# LightLinkV2.net
KiCad netlist of a schematic drawn in Altium Designer
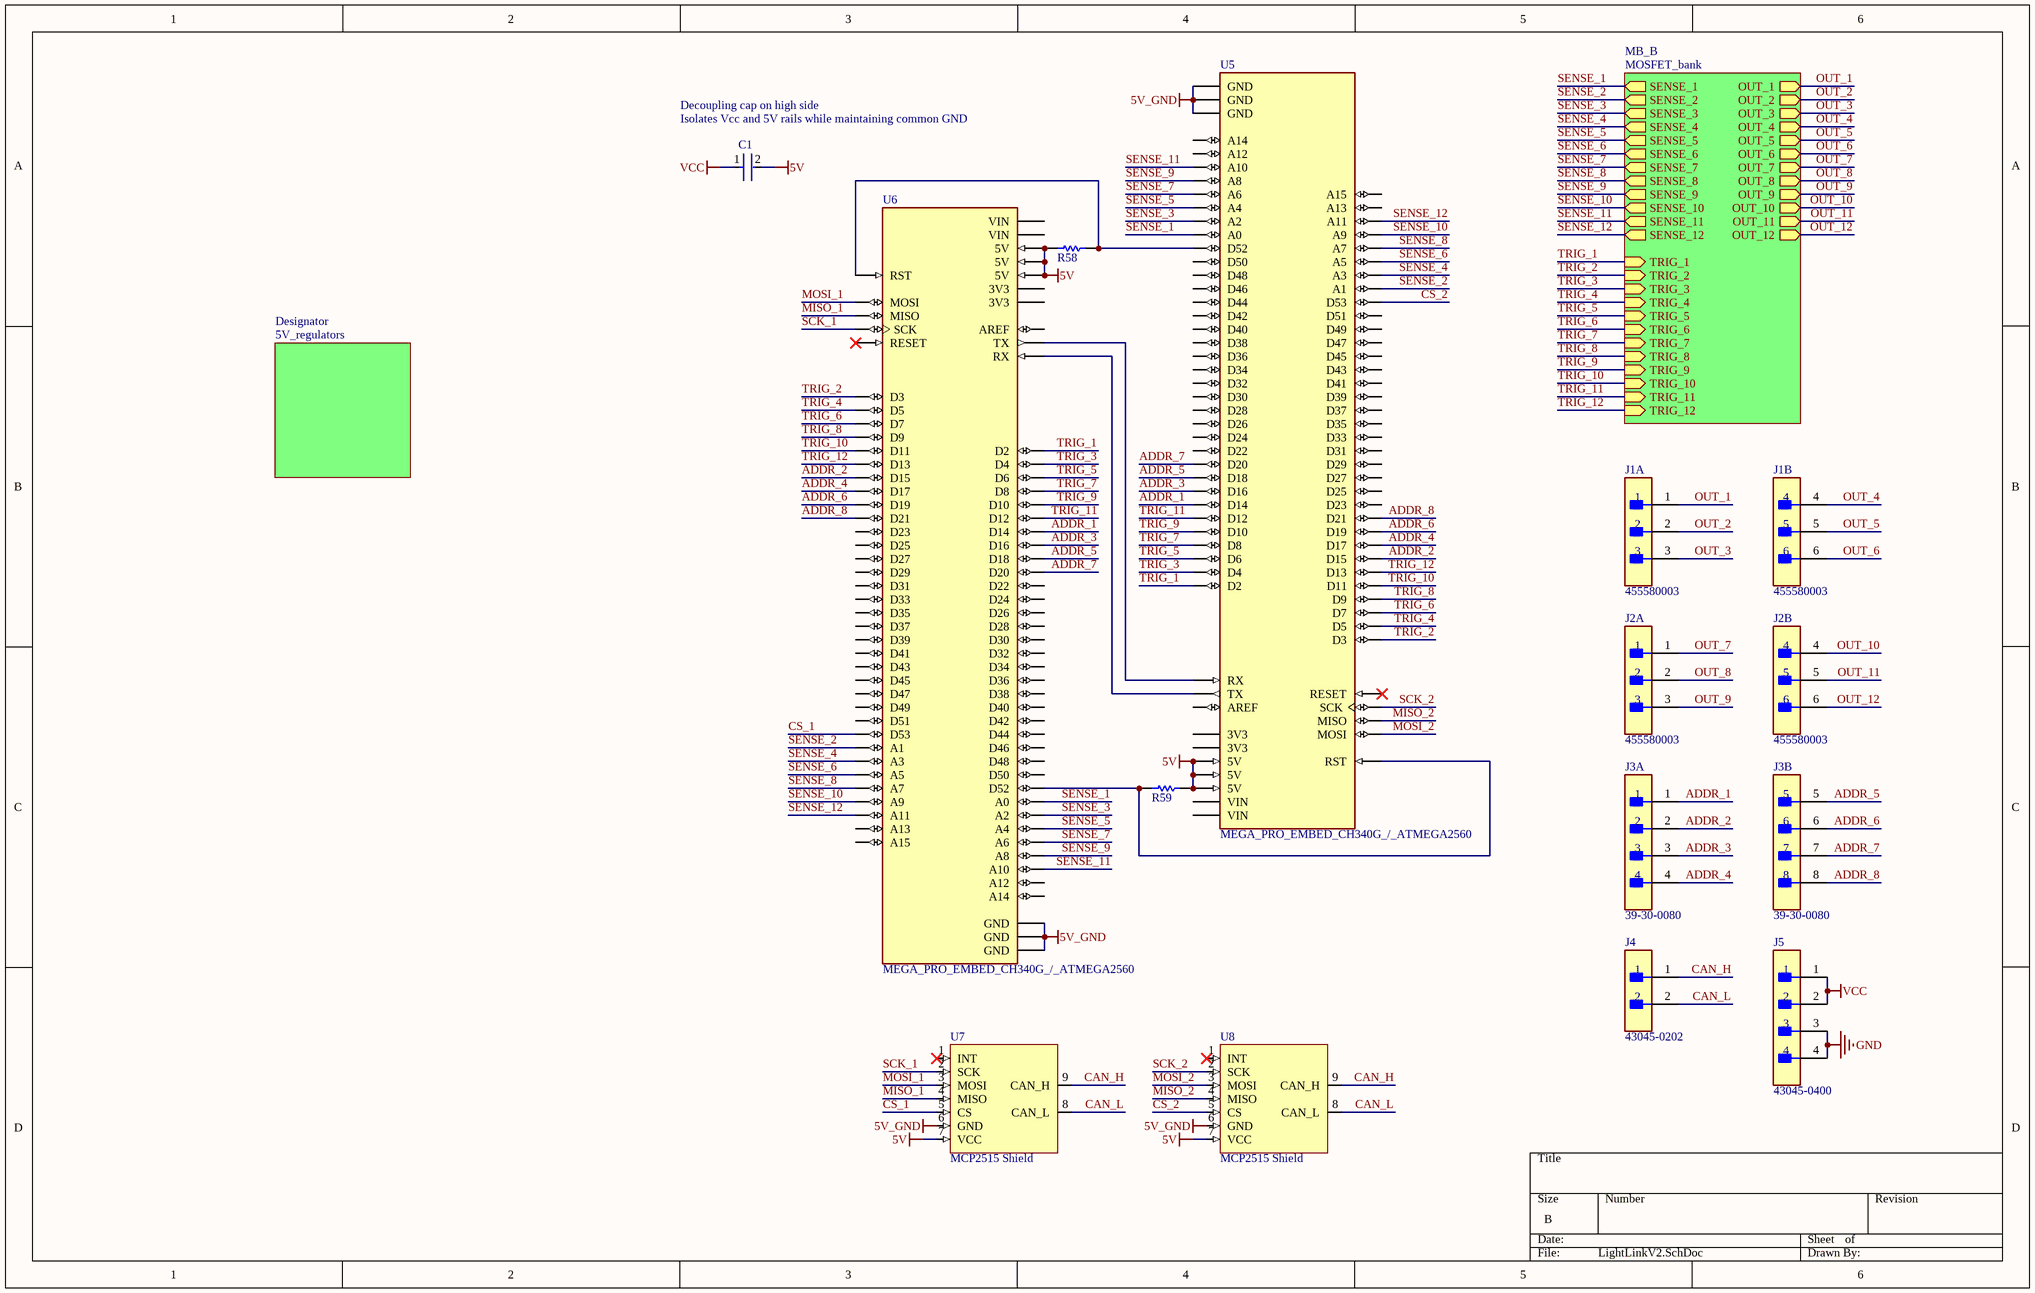
[diagram p0: LightLinkV2.SchDoc]

(export (version "E")
  (design (tool "Eeschema 10.0.6"))
  (components
    (comp (ref "C1")
      (value "C0603C103K5RACTU")
      (footprint "FP-C0603C-CF-MFG")
      (description "CAP CER 10000PF 50V X7R 0603")
      (fields
        (field (name "MANUFACTURER") "KEMET")
        (field (name "OCTOPART") "https://octopart.com/c0603c103k5ractu-kemet-133094")
      )
      (libsource (lib "Altium Content Vault") (part "b4654b650e69147ec39a6b967a45e02"))
    )
    (comp (ref "J1")
      (value "455580003")
      (footprint "FP-455580003-MFG")
      (description "CONN HEADER R/A 6POS 4.2MM")
      (fields
        (field (name "OCTOPART") "https://octopart.com/45558-0003-molex-7672845")
        (field (name "MANUFACTURER") "Molex")
      )
      (libsource (lib "Altium Content Vault") (part "bb9cbdb24149a20ba329b4e86909569"))
    )
    (comp (ref "J2")
      (value "455580003")
      (footprint "FP-455580003-MFG")
      (description "CONN HEADER R/A 6POS 4.2MM")
      (fields
        (field (name "OCTOPART") "https://octopart.com/45558-0003-molex-7672845")
        (field (name "MANUFACTURER") "Molex")
      )
      (libsource (lib "Altium Content Vault") (part "bb9cbdb24149a20ba329b4e86909569"))
    )
    (comp (ref "J3")
      (value "39-30-0080")
      (footprint "FP-39-30-0080-MFG")
      (description "CONN HEADER R/A 8POS 4.2MM")
      (libsource (lib "Altium Content Vault") (part "85438c39ca9ef07d43bb2e97c52bc44"))
    )
    (comp (ref "J4")
      (value "43045-0202")
      (footprint "FP-43045-0202-MFG")
      (description "CONN HEADER R/A 2POS")
      (libsource (lib "Altium Content Vault") (part "3bc925449376181038e59eaffc5286c"))
    )
    (comp (ref "J5")
      (value "43045-0400")
      (footprint "FP-43045-0400-MFG")
      (description "CONN HEADER R/A 4POS 3MM")
      (fields
        (field (name "MANUFACTURER") "Molex")
        (field (name "OCTOPART") "https://octopart.com/43045-0400-molex-287063")
      )
      (libsource (lib "Altium Content Vault") (part "c01754ab0efc13afb7424b896f394ef"))
    )
    (comp (ref "R58")
      (value "ERJ3EKF1002V")
      (footprint "RESC1609X55X30LL15T15")
      (description "Chip Resistor, 10 KOhm, +/- 1%, 0.1 W, -55 to 155 degC, 0603 (1608 Metric), RoHS, Tape and Reel")
      (fields (field (name "TOLERANCE") "1%") (field (name "MANUFACTURER") "Panasonic"))
      (libsource (lib "Altium Content Vault") (part "RES-2"))
    )
    (comp (ref "R59")
      (value "ERJ3EKF1002V")
      (footprint "RESC1609X55X30LL15T15")
      (description "Chip Resistor, 10 KOhm, +/- 1%, 0.1 W, -55 to 155 degC, 0603 (1608 Metric), RoHS, Tape and Reel")
      (fields (field (name "TOLERANCE") "1%") (field (name "MANUFACTURER") "Panasonic"))
      (libsource (lib "Altium Content Vault") (part "RES-2"))
    )
    (comp (ref "U5")
      (value "MEGA_PRO_EMBED_CH340G_/_ATMEGA2560")
      (footprint "MODULE_MEGA_PRO_EMBED_CH340G_/_ATMEGA2560")
      (description "Mega 2560 PRO (Embed) CH340G/ATmega2560-16AU")
      (libsource (lib "") (part "MEGA_PRO_EMBED_CH340G_/_ATMEGA2560_1"))
    )
    (comp (ref "U6")
      (value "MEGA_PRO_EMBED_CH340G_/_ATMEGA2560")
      (footprint "MODULE_MEGA_PRO_EMBED_CH340G_/_ATMEGA2560")
      (description "Mega 2560 PRO (Embed) CH340G/ATmega2560-16AU")
      (libsource (lib "uORocketry Hardware") (part "MEGA_PRO_EMBED_CH340G_/_ATMEGA2560"))
    )
    (comp (ref "U7")
      (value "MCP2515 Shield")
      (footprint "MCP2515 Shield-Footprint-1")
      (libsource (lib "uORocketry Hardware") (part "MCP2515 Shield Symbol"))
    )
    (comp (ref "U8")
      (value "MCP2515 Shield")
      (footprint "MCP2515 Shield-Footprint-1")
      (libsource (lib "uORocketry Hardware") (part "MCP2515 Shield Symbol"))
    )
  )
  (nets
    (net (code "1") (name "/ADDR_1") (class "Default")
      (node (ref "J3") (pin "1") (pinfunction "1_1") (pintype "passive"))
      (node (ref "U5") (pin "D14") (pinfunction "D14_D14") (pintype "bidirectional"))
      (node (ref "U6") (pin "D14") (pinfunction "D14_D14") (pintype "bidirectional"))
    )
    (net (code "2") (name "/ADDR_2") (class "Default")
      (node (ref "J3") (pin "2") (pinfunction "2_2") (pintype "passive"))
      (node (ref "U5") (pin "D15") (pinfunction "D15_D15") (pintype "bidirectional"))
      (node (ref "U6") (pin "D15") (pinfunction "D15_D15") (pintype "bidirectional"))
    )
    (net (code "3") (name "/ADDR_3") (class "Default")
      (node (ref "J3") (pin "3") (pinfunction "3_3") (pintype "passive"))
      (node (ref "U5") (pin "D16") (pinfunction "D16_D16") (pintype "bidirectional"))
      (node (ref "U6") (pin "D16") (pinfunction "D16_D16") (pintype "bidirectional"))
    )
    (net (code "4") (name "/ADDR_4") (class "Default")
      (node (ref "J3") (pin "4") (pinfunction "4_4") (pintype "passive"))
      (node (ref "U5") (pin "D17") (pinfunction "D17_D17") (pintype "bidirectional"))
      (node (ref "U6") (pin "D17") (pinfunction "D17_D17") (pintype "bidirectional"))
    )
    (net (code "5") (name "/ADDR_5") (class "Default")
      (node (ref "J3") (pin "5") (pinfunction "5_5") (pintype "passive"))
      (node (ref "U5") (pin "D18") (pinfunction "D18_D18") (pintype "bidirectional"))
      (node (ref "U6") (pin "D18") (pinfunction "D18_D18") (pintype "bidirectional"))
    )
    (net (code "6") (name "/ADDR_6") (class "Default")
      (node (ref "J3") (pin "6") (pinfunction "6_6") (pintype "passive"))
      (node (ref "U5") (pin "D19") (pinfunction "D19_D19") (pintype "bidirectional"))
      (node (ref "U6") (pin "D19") (pinfunction "D19_D19") (pintype "bidirectional"))
    )
    (net (code "7") (name "/ADDR_7") (class "Default")
      (node (ref "J3") (pin "7") (pinfunction "7_7") (pintype "passive"))
      (node (ref "U5") (pin "D20") (pinfunction "D20_D20") (pintype "bidirectional"))
      (node (ref "U6") (pin "D20") (pinfunction "D20_D20") (pintype "bidirectional"))
    )
    (net (code "8") (name "/ADDR_8") (class "Default")
      (node (ref "J3") (pin "8") (pinfunction "8_8") (pintype "passive"))
      (node (ref "U5") (pin "D21") (pinfunction "D21_D21") (pintype "bidirectional"))
      (node (ref "U6") (pin "D21") (pinfunction "D21_D21") (pintype "bidirectional"))
    )
    (net (code "9") (name "/CAN_H") (class "Default")
      (node (ref "J4") (pin "1") (pinfunction "1_1") (pintype "passive"))
      (node (ref "U7") (pin "9") (pinfunction "CAN_H_9") (pintype "bidirectional"))
      (node (ref "U8") (pin "9") (pinfunction "CAN_H_9") (pintype "bidirectional"))
    )
    (net (code "10") (name "/CAN_L") (class "Default")
      (node (ref "J4") (pin "2") (pinfunction "2_2") (pintype "passive"))
      (node (ref "U7") (pin "8") (pinfunction "CAN_L_8") (pintype "bidirectional"))
      (node (ref "U8") (pin "8") (pinfunction "CAN_L_8") (pintype "bidirectional"))
    )
    (net (code "11") (name "/CS_1") (class "Default")
      (node (ref "U6") (pin "D53") (pinfunction "D53_D53") (pintype "bidirectional"))
      (node (ref "U7") (pin "5") (pinfunction "CS_5") (pintype "input"))
    )
    (net (code "12") (name "/CS_2") (class "Default")
      (node (ref "U5") (pin "D53") (pinfunction "D53_D53") (pintype "bidirectional"))
      (node (ref "U8") (pin "5") (pinfunction "CS_5") (pintype "input"))
    )
    (net (code "13") (name "/MISO_1") (class "Default")
      (node (ref "U6") (pin "MISO") (pinfunction "MISO_MISO") (pintype "bidirectional"))
      (node (ref "U7") (pin "4") (pinfunction "MISO_4") (pintype "input"))
    )
    (net (code "14") (name "/MISO_2") (class "Default")
      (node (ref "U5") (pin "MISO") (pinfunction "MISO_MISO") (pintype "bidirectional"))
      (node (ref "U8") (pin "4") (pinfunction "MISO_4") (pintype "input"))
    )
    (net (code "15") (name "/MOSI_1") (class "Default")
      (node (ref "U6") (pin "MOSI") (pinfunction "MOSI_MOSI") (pintype "bidirectional"))
      (node (ref "U7") (pin "3") (pinfunction "MOSI_3") (pintype "input"))
    )
    (net (code "16") (name "/MOSI_2") (class "Default")
      (node (ref "U5") (pin "MOSI") (pinfunction "MOSI_MOSI") (pintype "bidirectional"))
      (node (ref "U8") (pin "3") (pinfunction "MOSI_3") (pintype "input"))
    )
    (net (code "17") (name "/OUT_1") (class "Default")
      (node (ref "J1") (pin "1") (pinfunction "1_1") (pintype "passive"))
    )
    (net (code "18") (name "/OUT_2") (class "Default")
      (node (ref "J1") (pin "2") (pinfunction "2_2") (pintype "passive"))
    )
    (net (code "19") (name "/OUT_3") (class "Default")
      (node (ref "J1") (pin "3") (pinfunction "3_3") (pintype "passive"))
    )
    (net (code "20") (name "/OUT_4") (class "Default")
      (node (ref "J1") (pin "4") (pinfunction "4_4") (pintype "passive"))
    )
    (net (code "21") (name "/OUT_5") (class "Default")
      (node (ref "J1") (pin "5") (pinfunction "5_5") (pintype "passive"))
    )
    (net (code "22") (name "/OUT_6") (class "Default")
      (node (ref "J1") (pin "6") (pinfunction "6_6") (pintype "passive"))
    )
    (net (code "23") (name "/OUT_7") (class "Default")
      (node (ref "J2") (pin "1") (pinfunction "1_1") (pintype "passive"))
    )
    (net (code "24") (name "/OUT_8") (class "Default")
      (node (ref "J2") (pin "2") (pinfunction "2_2") (pintype "passive"))
    )
    (net (code "25") (name "/OUT_9") (class "Default")
      (node (ref "J2") (pin "3") (pinfunction "3_3") (pintype "passive"))
    )
    (net (code "26") (name "/OUT_10") (class "Default")
      (node (ref "J2") (pin "4") (pinfunction "4_4") (pintype "passive"))
    )
    (net (code "27") (name "/OUT_11") (class "Default")
      (node (ref "J2") (pin "5") (pinfunction "5_5") (pintype "passive"))
    )
    (net (code "28") (name "/OUT_12") (class "Default")
      (node (ref "J2") (pin "6") (pinfunction "6_6") (pintype "passive"))
    )
    (net (code "29") (name "/SCK_1") (class "Default")
      (node (ref "U6") (pin "SCK") (pinfunction "SCK_SCK") (pintype "bidirectional"))
      (node (ref "U7") (pin "2") (pinfunction "SCK_2") (pintype "input"))
    )
    (net (code "30") (name "/SCK_2") (class "Default")
      (node (ref "U5") (pin "SCK") (pinfunction "SCK_SCK") (pintype "bidirectional"))
      (node (ref "U8") (pin "2") (pinfunction "SCK_2") (pintype "input"))
    )
    (net (code "31") (name "/SENSE_1") (class "Default")
      (node (ref "U5") (pin "A0") (pinfunction "A0_A0") (pintype "bidirectional"))
      (node (ref "U6") (pin "A0") (pinfunction "A0_A0") (pintype "bidirectional"))
    )
    (net (code "32") (name "/SENSE_2") (class "Default")
      (node (ref "U5") (pin "A1") (pinfunction "A1_A1") (pintype "bidirectional"))
      (node (ref "U6") (pin "A1") (pinfunction "A1_A1") (pintype "bidirectional"))
    )
    (net (code "33") (name "/SENSE_3") (class "Default")
      (node (ref "U5") (pin "A2") (pinfunction "A2_A2") (pintype "bidirectional"))
      (node (ref "U6") (pin "A2") (pinfunction "A2_A2") (pintype "bidirectional"))
    )
    (net (code "34") (name "/SENSE_4") (class "Default")
      (node (ref "U5") (pin "A3") (pinfunction "A3_A3") (pintype "bidirectional"))
      (node (ref "U6") (pin "A3") (pinfunction "A3_A3") (pintype "bidirectional"))
    )
    (net (code "35") (name "/SENSE_5") (class "Default")
      (node (ref "U5") (pin "A4") (pinfunction "A4_A4") (pintype "bidirectional"))
      (node (ref "U6") (pin "A4") (pinfunction "A4_A4") (pintype "bidirectional"))
    )
    (net (code "36") (name "/SENSE_6") (class "Default")
      (node (ref "U5") (pin "A5") (pinfunction "A5_A5") (pintype "bidirectional"))
      (node (ref "U6") (pin "A5") (pinfunction "A5_A5") (pintype "bidirectional"))
    )
    (net (code "37") (name "/SENSE_7") (class "Default")
      (node (ref "U5") (pin "A6") (pinfunction "A6_A6") (pintype "bidirectional"))
      (node (ref "U6") (pin "A6") (pinfunction "A6_A6") (pintype "bidirectional"))
    )
    (net (code "38") (name "/SENSE_8") (class "Default")
      (node (ref "U5") (pin "A7") (pinfunction "A7_A7") (pintype "bidirectional"))
      (node (ref "U6") (pin "A7") (pinfunction "A7_A7") (pintype "bidirectional"))
    )
    (net (code "39") (name "/SENSE_9") (class "Default")
      (node (ref "U5") (pin "A8") (pinfunction "A8_A8") (pintype "bidirectional"))
      (node (ref "U6") (pin "A8") (pinfunction "A8_A8") (pintype "bidirectional"))
    )
    (net (code "40") (name "/SENSE_10") (class "Default")
      (node (ref "U5") (pin "A9") (pinfunction "A9_A9") (pintype "bidirectional"))
      (node (ref "U6") (pin "A9") (pinfunction "A9_A9") (pintype "bidirectional"))
    )
    (net (code "41") (name "/SENSE_11") (class "Default")
      (node (ref "U5") (pin "A10") (pinfunction "A10_A10") (pintype "bidirectional"))
      (node (ref "U6") (pin "A10") (pinfunction "A10_A10") (pintype "bidirectional"))
    )
    (net (code "42") (name "/SENSE_12") (class "Default")
      (node (ref "U5") (pin "A11") (pinfunction "A11_A11") (pintype "bidirectional"))
      (node (ref "U6") (pin "A11") (pinfunction "A11_A11") (pintype "bidirectional"))
    )
    (net (code "43") (name "/TRIG_1") (class "Default")
      (node (ref "U5") (pin "D2") (pinfunction "D2_D2") (pintype "bidirectional"))
      (node (ref "U6") (pin "D2") (pinfunction "D2_D2") (pintype "bidirectional"))
    )
    (net (code "44") (name "/TRIG_2") (class "Default")
      (node (ref "U5") (pin "D3") (pinfunction "D3_D3") (pintype "bidirectional"))
      (node (ref "U6") (pin "D3") (pinfunction "D3_D3") (pintype "bidirectional"))
    )
    (net (code "45") (name "/TRIG_3") (class "Default")
      (node (ref "U5") (pin "D4") (pinfunction "D4_D4") (pintype "bidirectional"))
      (node (ref "U6") (pin "D4") (pinfunction "D4_D4") (pintype "bidirectional"))
    )
    (net (code "46") (name "/TRIG_4") (class "Default")
      (node (ref "U5") (pin "D5") (pinfunction "D5_D5") (pintype "bidirectional"))
      (node (ref "U6") (pin "D5") (pinfunction "D5_D5") (pintype "bidirectional"))
    )
    (net (code "47") (name "/TRIG_5") (class "Default")
      (node (ref "U5") (pin "D6") (pinfunction "D6_D6") (pintype "bidirectional"))
      (node (ref "U6") (pin "D6") (pinfunction "D6_D6") (pintype "bidirectional"))
    )
    (net (code "48") (name "/TRIG_6") (class "Default")
      (node (ref "U5") (pin "D7") (pinfunction "D7_D7") (pintype "bidirectional"))
      (node (ref "U6") (pin "D7") (pinfunction "D7_D7") (pintype "bidirectional"))
    )
    (net (code "49") (name "/TRIG_7") (class "Default")
      (node (ref "U5") (pin "D8") (pinfunction "D8_D8") (pintype "bidirectional"))
      (node (ref "U6") (pin "D8") (pinfunction "D8_D8") (pintype "bidirectional"))
    )
    (net (code "50") (name "/TRIG_8") (class "Default")
      (node (ref "U5") (pin "D9") (pinfunction "D9_D9") (pintype "bidirectional"))
      (node (ref "U6") (pin "D9") (pinfunction "D9_D9") (pintype "bidirectional"))
    )
    (net (code "51") (name "/TRIG_9") (class "Default")
      (node (ref "U5") (pin "D10") (pinfunction "D10_D10") (pintype "bidirectional"))
      (node (ref "U6") (pin "D10") (pinfunction "D10_D10") (pintype "bidirectional"))
    )
    (net (code "52") (name "/TRIG_10") (class "Default")
      (node (ref "U5") (pin "D11") (pinfunction "D11_D11") (pintype "bidirectional"))
      (node (ref "U6") (pin "D11") (pinfunction "D11_D11") (pintype "bidirectional"))
    )
    (net (code "53") (name "/TRIG_11") (class "Default")
      (node (ref "U5") (pin "D12") (pinfunction "D12_D12") (pintype "bidirectional"))
      (node (ref "U6") (pin "D12") (pinfunction "D12_D12") (pintype "bidirectional"))
    )
    (net (code "54") (name "/TRIG_12") (class "Default")
      (node (ref "U5") (pin "D13") (pinfunction "D13_D13") (pintype "bidirectional"))
      (node (ref "U6") (pin "D13") (pinfunction "D13_D13") (pintype "bidirectional"))
    )
    (net (code "55") (name "5V") (class "Default")
      (node (ref "C1") (pin "2") (pinfunction "2_2") (pintype "passive"))
      (node (ref "R58") (pin "2") (pinfunction "2_2") (pintype "passive"))
      (node (ref "R59") (pin "1") (pinfunction "1_1") (pintype "passive"))
      (node (ref "U5") (pin "5V_1") (pinfunction "5V_5V_1") (pintype "input"))
      (node (ref "U5") (pin "5V_2") (pinfunction "5V_5V_2") (pintype "input"))
      (node (ref "U5") (pin "5V_3") (pinfunction "5V_5V_3") (pintype "input"))
      (node (ref "U6") (pin "5V_1") (pinfunction "5V_5V_1") (pintype "input"))
      (node (ref "U6") (pin "5V_2") (pinfunction "5V_5V_2") (pintype "input"))
      (node (ref "U6") (pin "5V_3") (pinfunction "5V_5V_3") (pintype "input"))
      (node (ref "U7") (pin "7") (pinfunction "VCC_7") (pintype "input"))
      (node (ref "U8") (pin "7") (pinfunction "VCC_7") (pintype "input"))
    )
    (net (code "56") (name "5V_GND") (class "Default")
      (node (ref "U5") (pin "GND_1") (pinfunction "GND_GND_1") (pintype "power_in"))
      (node (ref "U5") (pin "GND_2") (pinfunction "GND_GND_2") (pintype "power_in"))
      (node (ref "U5") (pin "GND_3") (pinfunction "GND_GND_3") (pintype "power_in"))
      (node (ref "U6") (pin "GND_1") (pinfunction "GND_GND_1") (pintype "power_in"))
      (node (ref "U6") (pin "GND_2") (pinfunction "GND_GND_2") (pintype "power_in"))
      (node (ref "U6") (pin "GND_3") (pinfunction "GND_GND_3") (pintype "power_in"))
      (node (ref "U7") (pin "6") (pinfunction "GND_6") (pintype "input"))
      (node (ref "U8") (pin "6") (pinfunction "GND_6") (pintype "input"))
    )
    (net (code "57") (name "GND") (class "Default")
      (node (ref "J5") (pin "3") (pinfunction "3_3") (pintype "passive"))
      (node (ref "J5") (pin "4") (pinfunction "4_4") (pintype "passive"))
    )
    (net (code "58") (name "Net-(R58-Pad1)") (class "Default")
      (node (ref "R58") (pin "1") (pinfunction "1_1") (pintype "passive"))
      (node (ref "U5") (pin "D52") (pinfunction "D52_D52") (pintype "bidirectional"))
      (node (ref "U6") (pin "RST") (pinfunction "RST_RST") (pintype "input"))
    )
    (net (code "59") (name "Net-(R59-Pad2)") (class "Default")
      (node (ref "R59") (pin "2") (pinfunction "2_2") (pintype "passive"))
      (node (ref "U5") (pin "RST") (pinfunction "RST_RST") (pintype "input"))
      (node (ref "U6") (pin "D52") (pinfunction "D52_D52") (pintype "bidirectional"))
    )
    (net (code "60") (name "Net-(U5-PadRX)") (class "Default")
      (node (ref "U5") (pin "RX") (pinfunction "RX_RX") (pintype "input"))
      (node (ref "U6") (pin "TX") (pinfunction "TX_TX") (pintype "output"))
    )
    (net (code "61") (name "Net-(U5-PadTX)") (class "Default")
      (node (ref "U5") (pin "TX") (pinfunction "TX_TX") (pintype "output"))
      (node (ref "U6") (pin "RX") (pinfunction "RX_RX") (pintype "input"))
    )
    (net (code "62") (name "VCC") (class "Default")
      (node (ref "C1") (pin "1") (pinfunction "1_1") (pintype "passive"))
      (node (ref "J5") (pin "1") (pinfunction "1_1") (pintype "passive"))
      (node (ref "J5") (pin "2") (pinfunction "2_2") (pintype "passive"))
    )
    (net (code "63") (name "unconnected-(U5-3V3-Pad3V3_1)") (class "Default")
      (node (ref "U5") (pin "3V3_1") (pinfunction "3V3_3V3_1") (pintype "power_in"))
    )
    (net (code "64") (name "unconnected-(U5-3V3-Pad3V3_2)") (class "Default")
      (node (ref "U5") (pin "3V3_2") (pinfunction "3V3_3V3_2") (pintype "power_in"))
    )
    (net (code "65") (name "unconnected-(U5-PadA12)") (class "Default")
      (node (ref "U5") (pin "A12") (pinfunction "A12_A12") (pintype "bidirectional"))
    )
    (net (code "66") (name "unconnected-(U5-PadA13)") (class "Default")
      (node (ref "U5") (pin "A13") (pinfunction "A13_A13") (pintype "bidirectional"))
    )
    (net (code "67") (name "unconnected-(U5-PadA14)") (class "Default")
      (node (ref "U5") (pin "A14") (pinfunction "A14_A14") (pintype "bidirectional"))
    )
    (net (code "68") (name "unconnected-(U5-PadA15)") (class "Default")
      (node (ref "U5") (pin "A15") (pinfunction "A15_A15") (pintype "bidirectional"))
    )
    (net (code "69") (name "unconnected-(U5-PadAREF)") (class "Default")
      (node (ref "U5") (pin "AREF") (pinfunction "AREF_AREF") (pintype "bidirectional"))
    )
    (net (code "70") (name "unconnected-(U5-PadD22)") (class "Default")
      (node (ref "U5") (pin "D22") (pinfunction "D22_D22") (pintype "bidirectional"))
    )
    (net (code "71") (name "unconnected-(U5-PadD23)") (class "Default")
      (node (ref "U5") (pin "D23") (pinfunction "D23_D23") (pintype "bidirectional"))
    )
    (net (code "72") (name "unconnected-(U5-PadD24)") (class "Default")
      (node (ref "U5") (pin "D24") (pinfunction "D24_D24") (pintype "bidirectional"))
    )
    (net (code "73") (name "unconnected-(U5-PadD25)") (class "Default")
      (node (ref "U5") (pin "D25") (pinfunction "D25_D25") (pintype "bidirectional"))
    )
    (net (code "74") (name "unconnected-(U5-PadD26)") (class "Default")
      (node (ref "U5") (pin "D26") (pinfunction "D26_D26") (pintype "bidirectional"))
    )
    (net (code "75") (name "unconnected-(U5-PadD27)") (class "Default")
      (node (ref "U5") (pin "D27") (pinfunction "D27_D27") (pintype "bidirectional"))
    )
    (net (code "76") (name "unconnected-(U5-PadD28)") (class "Default")
      (node (ref "U5") (pin "D28") (pinfunction "D28_D28") (pintype "bidirectional"))
    )
    (net (code "77") (name "unconnected-(U5-PadD29)") (class "Default")
      (node (ref "U5") (pin "D29") (pinfunction "D29_D29") (pintype "bidirectional"))
    )
    (net (code "78") (name "unconnected-(U5-PadD30)") (class "Default")
      (node (ref "U5") (pin "D30") (pinfunction "D30_D30") (pintype "bidirectional"))
    )
    (net (code "79") (name "unconnected-(U5-PadD31)") (class "Default")
      (node (ref "U5") (pin "D31") (pinfunction "D31_D31") (pintype "bidirectional"))
    )
    (net (code "80") (name "unconnected-(U5-PadD32)") (class "Default")
      (node (ref "U5") (pin "D32") (pinfunction "D32_D32") (pintype "bidirectional"))
    )
    (net (code "81") (name "unconnected-(U5-PadD33)") (class "Default")
      (node (ref "U5") (pin "D33") (pinfunction "D33_D33") (pintype "bidirectional"))
    )
    (net (code "82") (name "unconnected-(U5-PadD34)") (class "Default")
      (node (ref "U5") (pin "D34") (pinfunction "D34_D34") (pintype "bidirectional"))
    )
    (net (code "83") (name "unconnected-(U5-PadD35)") (class "Default")
      (node (ref "U5") (pin "D35") (pinfunction "D35_D35") (pintype "bidirectional"))
    )
    (net (code "84") (name "unconnected-(U5-PadD36)") (class "Default")
      (node (ref "U5") (pin "D36") (pinfunction "D36_D36") (pintype "bidirectional"))
    )
    (net (code "85") (name "unconnected-(U5-PadD37)") (class "Default")
      (node (ref "U5") (pin "D37") (pinfunction "D37_D37") (pintype "bidirectional"))
    )
    (net (code "86") (name "unconnected-(U5-PadD38)") (class "Default")
      (node (ref "U5") (pin "D38") (pinfunction "D38_D38") (pintype "bidirectional"))
    )
    (net (code "87") (name "unconnected-(U5-PadD39)") (class "Default")
      (node (ref "U5") (pin "D39") (pinfunction "D39_D39") (pintype "bidirectional"))
    )
    (net (code "88") (name "unconnected-(U5-PadD40)") (class "Default")
      (node (ref "U5") (pin "D40") (pinfunction "D40_D40") (pintype "bidirectional"))
    )
    (net (code "89") (name "unconnected-(U5-PadD41)") (class "Default")
      (node (ref "U5") (pin "D41") (pinfunction "D41_D41") (pintype "bidirectional"))
    )
    (net (code "90") (name "unconnected-(U5-PadD42)") (class "Default")
      (node (ref "U5") (pin "D42") (pinfunction "D42_D42") (pintype "bidirectional"))
    )
    (net (code "91") (name "unconnected-(U5-PadD43)") (class "Default")
      (node (ref "U5") (pin "D43") (pinfunction "D43_D43") (pintype "bidirectional"))
    )
    (net (code "92") (name "unconnected-(U5-PadD44)") (class "Default")
      (node (ref "U5") (pin "D44") (pinfunction "D44_D44") (pintype "bidirectional"))
    )
    (net (code "93") (name "unconnected-(U5-PadD45)") (class "Default")
      (node (ref "U5") (pin "D45") (pinfunction "D45_D45") (pintype "bidirectional"))
    )
    (net (code "94") (name "unconnected-(U5-PadD46)") (class "Default")
      (node (ref "U5") (pin "D46") (pinfunction "D46_D46") (pintype "bidirectional"))
    )
    (net (code "95") (name "unconnected-(U5-PadD47)") (class "Default")
      (node (ref "U5") (pin "D47") (pinfunction "D47_D47") (pintype "bidirectional"))
    )
    (net (code "96") (name "unconnected-(U5-PadD48)") (class "Default")
      (node (ref "U5") (pin "D48") (pinfunction "D48_D48") (pintype "bidirectional"))
    )
    (net (code "97") (name "unconnected-(U5-PadD49)") (class "Default")
      (node (ref "U5") (pin "D49") (pinfunction "D49_D49") (pintype "bidirectional"))
    )
    (net (code "98") (name "unconnected-(U5-PadD50)") (class "Default")
      (node (ref "U5") (pin "D50") (pinfunction "D50_D50") (pintype "bidirectional"))
    )
    (net (code "99") (name "unconnected-(U5-PadD51)") (class "Default")
      (node (ref "U5") (pin "D51") (pinfunction "D51_D51") (pintype "bidirectional"))
    )
    (net (code "100") (name "unconnected-(U5-PadRESET)") (class "Default")
      (node (ref "U5") (pin "RESET") (pinfunction "RESET_RESET") (pintype "input+no_connect"))
    )
    (net (code "101") (name "unconnected-(U5-VIN-PadVIN_1)") (class "Default")
      (node (ref "U5") (pin "VIN_1") (pinfunction "VIN_VIN_1") (pintype "power_in"))
    )
    (net (code "102") (name "unconnected-(U5-VIN-PadVIN_2)") (class "Default")
      (node (ref "U5") (pin "VIN_2") (pinfunction "VIN_VIN_2") (pintype "power_in"))
    )
    (net (code "103") (name "unconnected-(U6-3V3-Pad3V3_1)") (class "Default")
      (node (ref "U6") (pin "3V3_1") (pinfunction "3V3_3V3_1") (pintype "power_in"))
    )
    (net (code "104") (name "unconnected-(U6-3V3-Pad3V3_2)") (class "Default")
      (node (ref "U6") (pin "3V3_2") (pinfunction "3V3_3V3_2") (pintype "power_in"))
    )
    (net (code "105") (name "unconnected-(U6-PadA12)") (class "Default")
      (node (ref "U6") (pin "A12") (pinfunction "A12_A12") (pintype "bidirectional"))
    )
    (net (code "106") (name "unconnected-(U6-PadA13)") (class "Default")
      (node (ref "U6") (pin "A13") (pinfunction "A13_A13") (pintype "bidirectional"))
    )
    (net (code "107") (name "unconnected-(U6-PadA14)") (class "Default")
      (node (ref "U6") (pin "A14") (pinfunction "A14_A14") (pintype "bidirectional"))
    )
    (net (code "108") (name "unconnected-(U6-PadA15)") (class "Default")
      (node (ref "U6") (pin "A15") (pinfunction "A15_A15") (pintype "bidirectional"))
    )
    (net (code "109") (name "unconnected-(U6-PadAREF)") (class "Default")
      (node (ref "U6") (pin "AREF") (pinfunction "AREF_AREF") (pintype "bidirectional"))
    )
    (net (code "110") (name "unconnected-(U6-PadD22)") (class "Default")
      (node (ref "U6") (pin "D22") (pinfunction "D22_D22") (pintype "bidirectional"))
    )
    (net (code "111") (name "unconnected-(U6-PadD23)") (class "Default")
      (node (ref "U6") (pin "D23") (pinfunction "D23_D23") (pintype "bidirectional"))
    )
    (net (code "112") (name "unconnected-(U6-PadD24)") (class "Default")
      (node (ref "U6") (pin "D24") (pinfunction "D24_D24") (pintype "bidirectional"))
    )
    (net (code "113") (name "unconnected-(U6-PadD25)") (class "Default")
      (node (ref "U6") (pin "D25") (pinfunction "D25_D25") (pintype "bidirectional"))
    )
    (net (code "114") (name "unconnected-(U6-PadD26)") (class "Default")
      (node (ref "U6") (pin "D26") (pinfunction "D26_D26") (pintype "bidirectional"))
    )
    (net (code "115") (name "unconnected-(U6-PadD27)") (class "Default")
      (node (ref "U6") (pin "D27") (pinfunction "D27_D27") (pintype "bidirectional"))
    )
    (net (code "116") (name "unconnected-(U6-PadD28)") (class "Default")
      (node (ref "U6") (pin "D28") (pinfunction "D28_D28") (pintype "bidirectional"))
    )
    (net (code "117") (name "unconnected-(U6-PadD29)") (class "Default")
      (node (ref "U6") (pin "D29") (pinfunction "D29_D29") (pintype "bidirectional"))
    )
    (net (code "118") (name "unconnected-(U6-PadD30)") (class "Default")
      (node (ref "U6") (pin "D30") (pinfunction "D30_D30") (pintype "bidirectional"))
    )
    (net (code "119") (name "unconnected-(U6-PadD31)") (class "Default")
      (node (ref "U6") (pin "D31") (pinfunction "D31_D31") (pintype "bidirectional"))
    )
    (net (code "120") (name "unconnected-(U6-PadD32)") (class "Default")
      (node (ref "U6") (pin "D32") (pinfunction "D32_D32") (pintype "bidirectional"))
    )
    (net (code "121") (name "unconnected-(U6-PadD33)") (class "Default")
      (node (ref "U6") (pin "D33") (pinfunction "D33_D33") (pintype "bidirectional"))
    )
    (net (code "122") (name "unconnected-(U6-PadD34)") (class "Default")
      (node (ref "U6") (pin "D34") (pinfunction "D34_D34") (pintype "bidirectional"))
    )
    (net (code "123") (name "unconnected-(U6-PadD35)") (class "Default")
      (node (ref "U6") (pin "D35") (pinfunction "D35_D35") (pintype "bidirectional"))
    )
    (net (code "124") (name "unconnected-(U6-PadD36)") (class "Default")
      (node (ref "U6") (pin "D36") (pinfunction "D36_D36") (pintype "bidirectional"))
    )
    (net (code "125") (name "unconnected-(U6-PadD37)") (class "Default")
      (node (ref "U6") (pin "D37") (pinfunction "D37_D37") (pintype "bidirectional"))
    )
    (net (code "126") (name "unconnected-(U6-PadD38)") (class "Default")
      (node (ref "U6") (pin "D38") (pinfunction "D38_D38") (pintype "bidirectional"))
    )
    (net (code "127") (name "unconnected-(U6-PadD39)") (class "Default")
      (node (ref "U6") (pin "D39") (pinfunction "D39_D39") (pintype "bidirectional"))
    )
    (net (code "128") (name "unconnected-(U6-PadD40)") (class "Default")
      (node (ref "U6") (pin "D40") (pinfunction "D40_D40") (pintype "bidirectional"))
    )
    (net (code "129") (name "unconnected-(U6-PadD41)") (class "Default")
      (node (ref "U6") (pin "D41") (pinfunction "D41_D41") (pintype "bidirectional"))
    )
    (net (code "130") (name "unconnected-(U6-PadD42)") (class "Default")
      (node (ref "U6") (pin "D42") (pinfunction "D42_D42") (pintype "bidirectional"))
    )
    (net (code "131") (name "unconnected-(U6-PadD43)") (class "Default")
      (node (ref "U6") (pin "D43") (pinfunction "D43_D43") (pintype "bidirectional"))
    )
    (net (code "132") (name "unconnected-(U6-PadD44)") (class "Default")
      (node (ref "U6") (pin "D44") (pinfunction "D44_D44") (pintype "bidirectional"))
    )
    (net (code "133") (name "unconnected-(U6-PadD45)") (class "Default")
      (node (ref "U6") (pin "D45") (pinfunction "D45_D45") (pintype "bidirectional"))
    )
    (net (code "134") (name "unconnected-(U6-PadD46)") (class "Default")
      (node (ref "U6") (pin "D46") (pinfunction "D46_D46") (pintype "bidirectional"))
    )
    (net (code "135") (name "unconnected-(U6-PadD47)") (class "Default")
      (node (ref "U6") (pin "D47") (pinfunction "D47_D47") (pintype "bidirectional"))
    )
    (net (code "136") (name "unconnected-(U6-PadD48)") (class "Default")
      (node (ref "U6") (pin "D48") (pinfunction "D48_D48") (pintype "bidirectional"))
    )
    (net (code "137") (name "unconnected-(U6-PadD49)") (class "Default")
      (node (ref "U6") (pin "D49") (pinfunction "D49_D49") (pintype "bidirectional"))
    )
    (net (code "138") (name "unconnected-(U6-PadD50)") (class "Default")
      (node (ref "U6") (pin "D50") (pinfunction "D50_D50") (pintype "bidirectional"))
    )
    (net (code "139") (name "unconnected-(U6-PadD51)") (class "Default")
      (node (ref "U6") (pin "D51") (pinfunction "D51_D51") (pintype "bidirectional"))
    )
    (net (code "140") (name "unconnected-(U6-PadRESET)") (class "Default")
      (node (ref "U6") (pin "RESET") (pinfunction "RESET_RESET") (pintype "input+no_connect"))
    )
    (net (code "141") (name "unconnected-(U6-VIN-PadVIN_1)") (class "Default")
      (node (ref "U6") (pin "VIN_1") (pinfunction "VIN_VIN_1") (pintype "power_in"))
    )
    (net (code "142") (name "unconnected-(U6-VIN-PadVIN_2)") (class "Default")
      (node (ref "U6") (pin "VIN_2") (pinfunction "VIN_VIN_2") (pintype "power_in"))
    )
    (net (code "143") (name "unconnected-(U7-INT-Pad1)") (class "Default")
      (node (ref "U7") (pin "1") (pinfunction "INT_1") (pintype "input+no_connect"))
    )
    (net (code "144") (name "unconnected-(U8-INT-Pad1)") (class "Default")
      (node (ref "U8") (pin "1") (pinfunction "INT_1") (pintype "input+no_connect"))
    )
  )
)
